# DDS_OUT_channel.net
KiCad netlist of a schematic drawn in Altium Designer
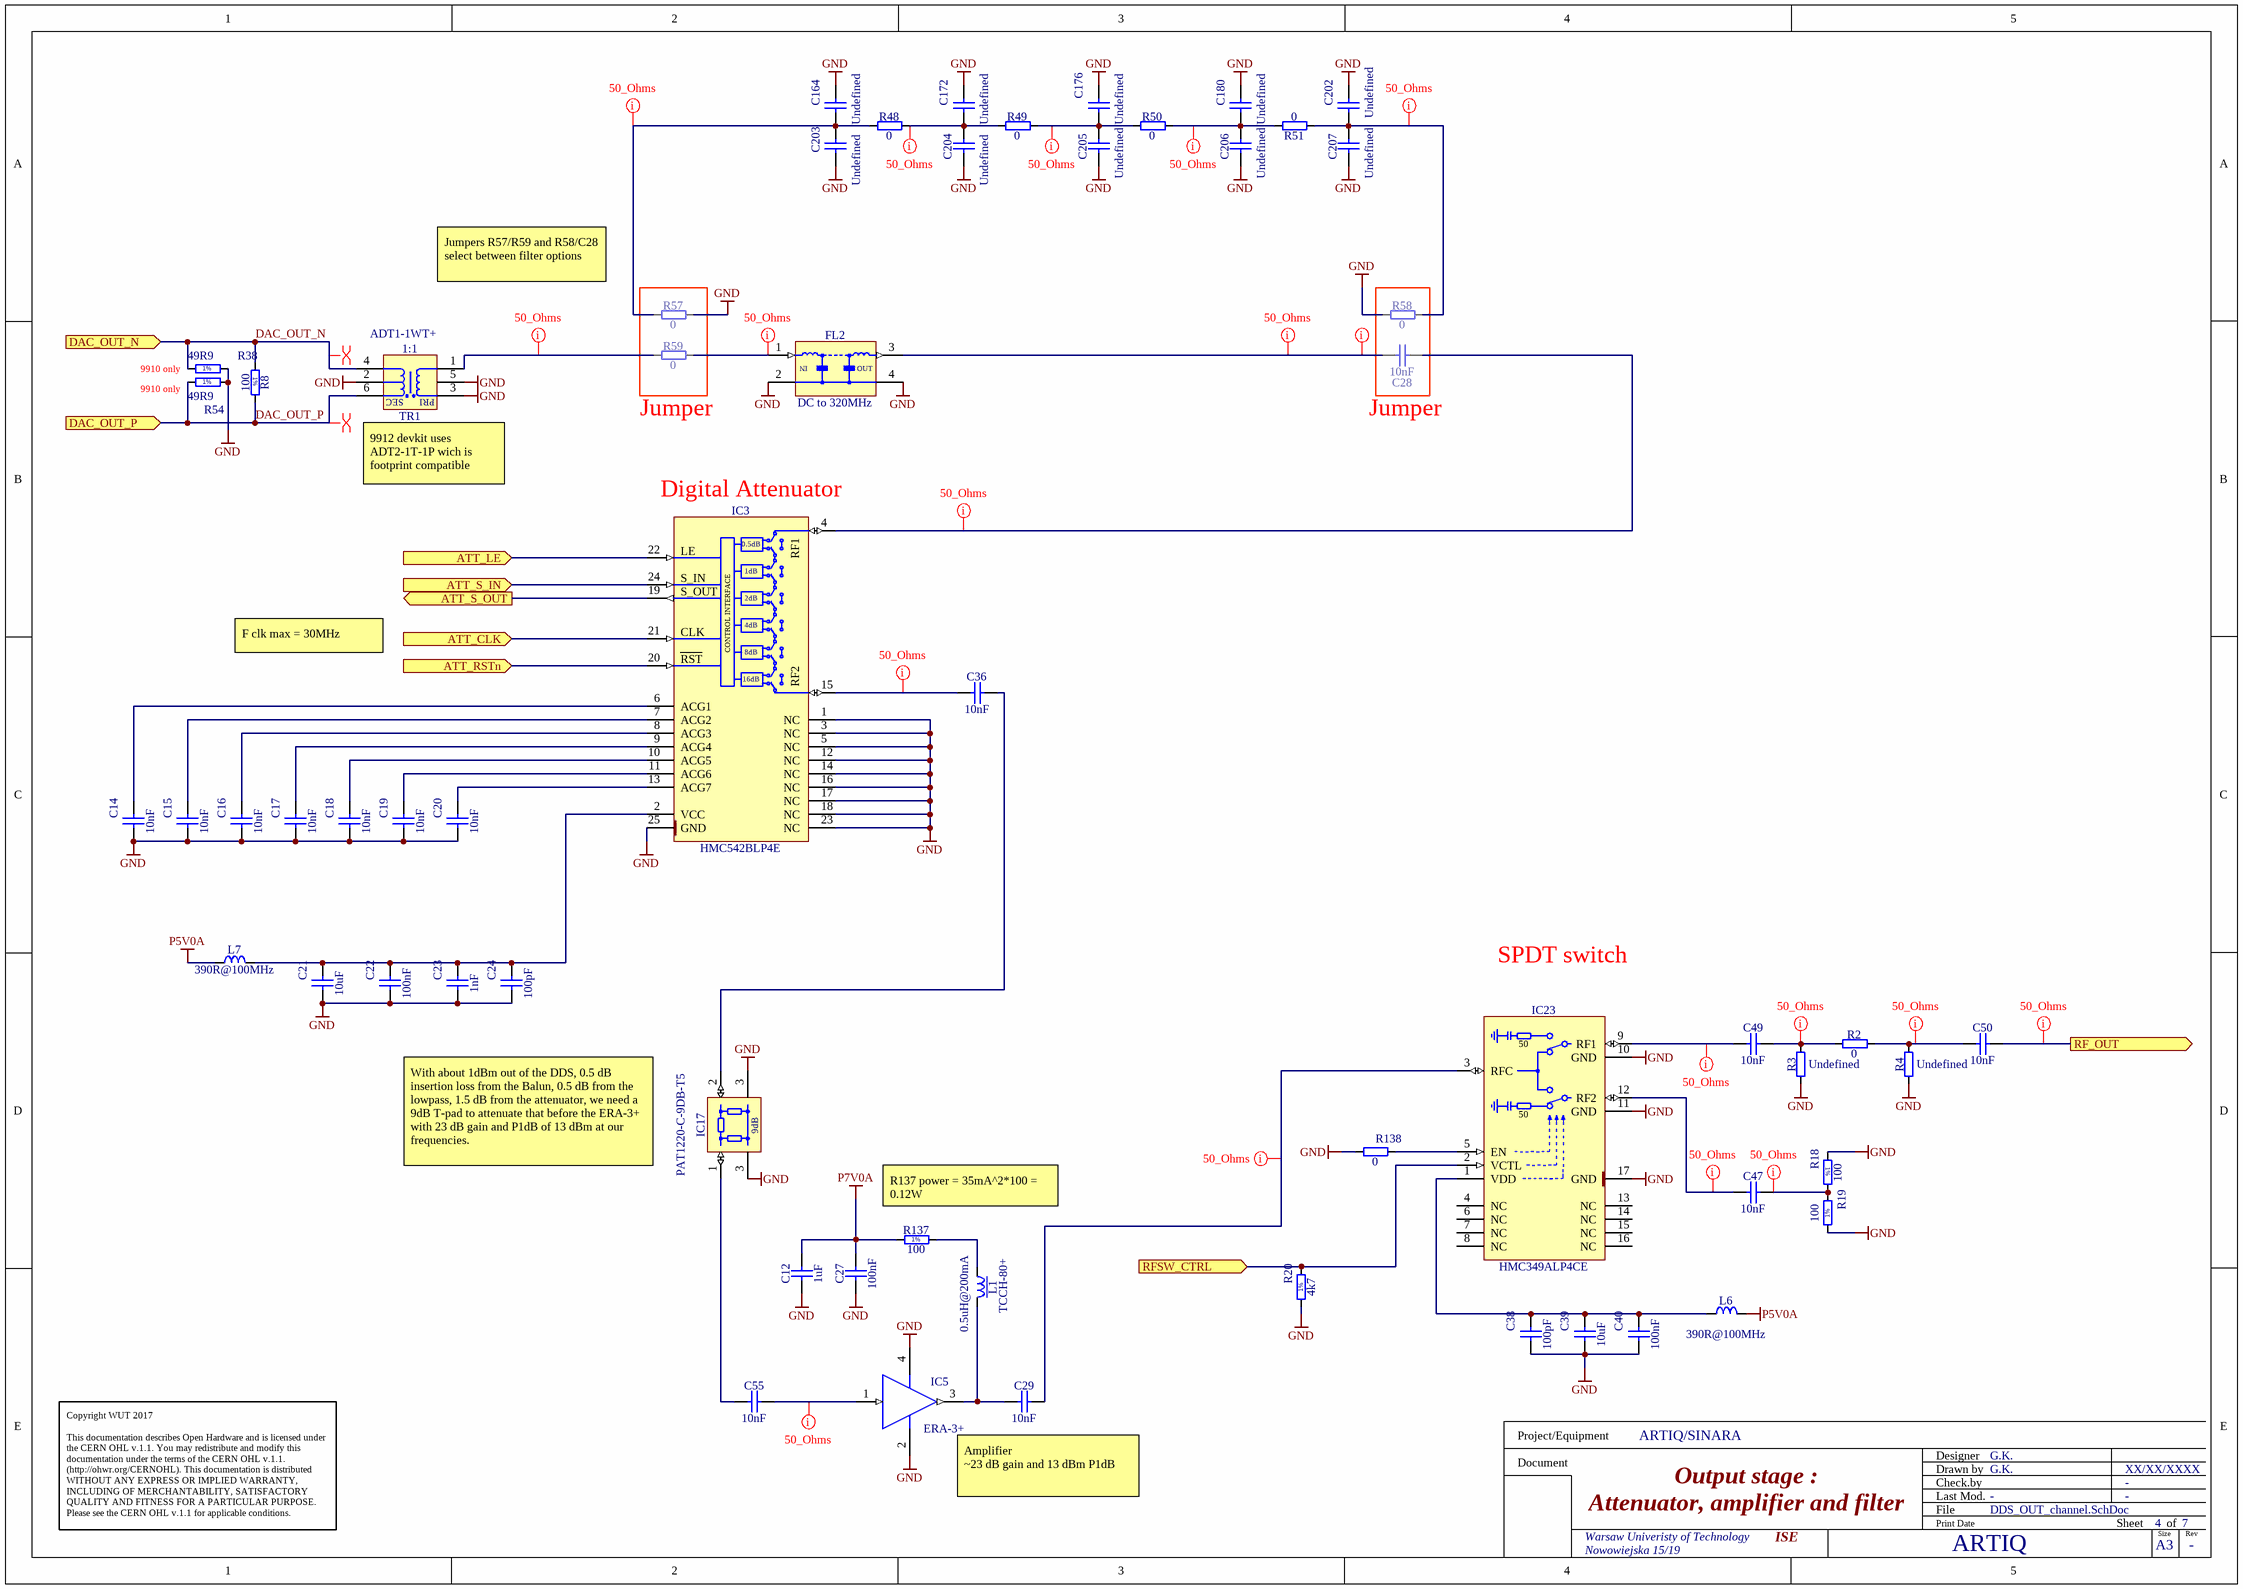
[diagram p0: DDS_OUT_channel.SchDoc]

(export (version "E")
  (design (tool "Eeschema 10.0.6"))
  (components
    (comp (ref "C12")
      (value "1uF")
      (footprint "CAPC2012X140N")
      (description "Non-polarised capacitor")
      (fields
        (field (name "PART NUMBER") "CC0805_1UF_35V_20%_X7R")
        (field (name "VOLTAGE") "35V")
        (field (name "AUTHOR") "CERN DEM JLC")
      )
      (libsource (lib "Capacitors") (part "Capacitor - non polarized"))
    )
    (comp (ref "C14")
      (value "10nF")
      (footprint "CAPC1005X55N")
      (description "Non-polarised capacitor")
      (fields
        (field (name "PART NUMBER") "CC0402_10NF_16V_10%_X7R")
        (field (name "VOLTAGE") "16V")
        (field (name "AUTHOR") "CERN DEM JLC")
      )
      (libsource (lib "Capacitors") (part "Capacitor - non polarized"))
    )
    (comp (ref "C15")
      (value "10nF")
      (footprint "CAPC1005X55N")
      (description "Non-polarised capacitor")
      (fields
        (field (name "PART NUMBER") "CC0402_10NF_16V_10%_X7R")
        (field (name "VOLTAGE") "16V")
        (field (name "AUTHOR") "CERN DEM JLC")
      )
      (libsource (lib "Capacitors") (part "Capacitor - non polarized"))
    )
    (comp (ref "C16")
      (value "10nF")
      (footprint "CAPC1005X55N")
      (description "Non-polarised capacitor")
      (fields
        (field (name "PART NUMBER") "CC0402_10NF_16V_10%_X7R")
        (field (name "VOLTAGE") "16V")
        (field (name "AUTHOR") "CERN DEM JLC")
      )
      (libsource (lib "Capacitors") (part "Capacitor - non polarized"))
    )
    (comp (ref "C17")
      (value "10nF")
      (footprint "CAPC1005X55N")
      (description "Non-polarised capacitor")
      (fields
        (field (name "PART NUMBER") "CC0402_10NF_16V_10%_X7R")
        (field (name "VOLTAGE") "16V")
        (field (name "AUTHOR") "CERN DEM JLC")
      )
      (libsource (lib "Capacitors") (part "Capacitor - non polarized"))
    )
    (comp (ref "C18")
      (value "10nF")
      (footprint "CAPC1005X55N")
      (description "Non-polarised capacitor")
      (fields
        (field (name "PART NUMBER") "CC0402_10NF_16V_10%_X7R")
        (field (name "VOLTAGE") "16V")
        (field (name "AUTHOR") "CERN DEM JLC")
      )
      (libsource (lib "Capacitors") (part "Capacitor - non polarized"))
    )
    (comp (ref "C19")
      (value "10nF")
      (footprint "CAPC1005X55N")
      (description "Non-polarised capacitor")
      (fields
        (field (name "PART NUMBER") "CC0402_10NF_16V_10%_X7R")
        (field (name "VOLTAGE") "16V")
        (field (name "AUTHOR") "CERN DEM JLC")
      )
      (libsource (lib "Capacitors") (part "Capacitor - non polarized"))
    )
    (comp (ref "C20")
      (value "10nF")
      (footprint "CAPC1005X55N")
      (description "Non-polarised capacitor")
      (fields
        (field (name "PART NUMBER") "CC0402_10NF_16V_10%_X7R")
        (field (name "VOLTAGE") "16V")
        (field (name "AUTHOR") "CERN DEM JLC")
      )
      (libsource (lib "Capacitors") (part "Capacitor - non polarized"))
    )
    (comp (ref "C21")
      (value "10uF")
      (footprint "CAPC1608X80N")
      (description "Non-polarised capacitor")
      (fields
        (field (name "PART NUMBER") "CC0603_10UF_16V_20%_X5R")
        (field (name "VOLTAGE") "16V")
        (field (name "AUTHOR") "CERN DEM MR")
      )
      (libsource (lib "Capacitors") (part "Capacitor - non polarized"))
    )
    (comp (ref "C22")
      (value "100nF")
      (footprint "CAPC1005X55N")
      (description "Non-polarised capacitor")
      (fields
        (field (name "PART NUMBER") "CC0402_100NF_16V_10%_X7R")
        (field (name "VOLTAGE") "16V")
        (field (name "AUTHOR") "CERN DEM JLC")
      )
      (libsource (lib "Capacitors") (part "Capacitor - non polarized"))
    )
    (comp (ref "C23")
      (value "1nF")
      (footprint "CAPC1005X55N")
      (description "Non-polarised capacitor")
      (fields
        (field (name "PART NUMBER") "CC0402_1NF_50V_10%_X7R")
        (field (name "VOLTAGE") "50V")
        (field (name "AUTHOR") "CERN DEM JLC")
      )
      (libsource (lib "Capacitors") (part "Capacitor - non polarized"))
    )
    (comp (ref "C24")
      (value "100pF")
      (footprint "CAPC1005X55N")
      (description "Non-polarised capacitor")
      (fields
        (field (name "PART NUMBER") "CC0402_100PF_50V_5%_C0G")
        (field (name "VOLTAGE") "50V")
        (field (name "AUTHOR") "CERN DEM JLC")
      )
      (libsource (lib "Capacitors") (part "Capacitor - non polarized"))
    )
    (comp (ref "C27")
      (value "100nF")
      (footprint "CAPC1005X55N")
      (description "Non-polarised capacitor")
      (fields
        (field (name "PART NUMBER") "CC0402_100NF_16V_10%_X5R")
        (field (name "VOLTAGE") "16V")
        (field (name "AUTHOR") "CERN DEM JLC")
      )
      (libsource (lib "Capacitors") (part "Capacitor - non polarized"))
    )
    (comp (ref "C28")
      (value "10nF")
      (footprint "CAPC1005X55N")
      (description "Non-polarised capacitor")
      (fields
        (field (name "PART NUMBER") "CC0402_10NF_16V_10%_X7R")
        (field (name "VOLTAGE") "16V")
        (field (name "AUTHOR") "CERN DEM JLC")
      )
      (libsource (lib "Capacitors") (part "Capacitor - non polarized"))
    )
    (comp (ref "C29")
      (value "10nF")
      (footprint "CAPC1005X55N")
      (description "Non-polarised capacitor")
      (fields
        (field (name "PART NUMBER") "CC0402_10NF_16V_10%_X7R")
        (field (name "VOLTAGE") "16V")
        (field (name "AUTHOR") "CERN DEM JLC")
      )
      (libsource (lib "Capacitors") (part "Capacitor - non polarized"))
    )
    (comp (ref "C36")
      (value "10nF")
      (footprint "CAPC1005X55N")
      (description "Non-polarised capacitor")
      (fields
        (field (name "PART NUMBER") "CC0402_10NF_16V_10%_X7R")
        (field (name "VOLTAGE") "16V")
        (field (name "AUTHOR") "CERN DEM JLC")
      )
      (libsource (lib "Capacitors") (part "Capacitor - non polarized"))
    )
    (comp (ref "C38")
      (value "100pF")
      (footprint "CAPC1005X55N")
      (description "Non-polarised capacitor")
      (fields
        (field (name "PART NUMBER") "CC0402_100PF_50V_5%_C0G")
        (field (name "VOLTAGE") "50V")
        (field (name "AUTHOR") "CERN DEM JLC")
      )
      (libsource (lib "Capacitors") (part "Capacitor - non polarized"))
    )
    (comp (ref "C39")
      (value "10uF")
      (footprint "CAPC1608X80N")
      (description "Non-polarised capacitor")
      (fields
        (field (name "PART NUMBER") "CC0603_10UF_16V_20%_X5R")
        (field (name "VOLTAGE") "16V")
        (field (name "AUTHOR") "CERN DEM MR")
      )
      (libsource (lib "Capacitors") (part "Capacitor - non polarized"))
    )
    (comp (ref "C40")
      (value "100nF")
      (footprint "CAPC1005X55N")
      (description "Non-polarised capacitor")
      (fields
        (field (name "PART NUMBER") "CC0402_100NF_16V_10%_X5R")
        (field (name "VOLTAGE") "16V")
        (field (name "AUTHOR") "CERN DEM JLC")
      )
      (libsource (lib "Capacitors") (part "Capacitor - non polarized"))
    )
    (comp (ref "C47")
      (value "10nF")
      (footprint "CAPC1005X55N")
      (description "Non-polarised capacitor")
      (fields
        (field (name "PART NUMBER") "CC0402_10NF_16V_10%_X7R")
        (field (name "VOLTAGE") "16V")
        (field (name "AUTHOR") "CERN DEM JLC")
      )
      (libsource (lib "Capacitors") (part "Capacitor - non polarized"))
    )
    (comp (ref "C49")
      (value "10nF")
      (footprint "CAPC1005X55N")
      (description "Non-polarised capacitor")
      (fields
        (field (name "PART NUMBER") "CC0402_10NF_16V_10%_X7R")
        (field (name "VOLTAGE") "16V")
        (field (name "AUTHOR") "CERN DEM JLC")
      )
      (libsource (lib "Capacitors") (part "Capacitor - non polarized"))
    )
    (comp (ref "C50")
      (value "10nF")
      (footprint "CAPC1005X55N")
      (description "Non-polarised capacitor")
      (fields
        (field (name "PART NUMBER") "CC0402_10NF_16V_10%_X7R")
        (field (name "VOLTAGE") "16V")
        (field (name "AUTHOR") "CERN DEM JLC")
      )
      (libsource (lib "Capacitors") (part "Capacitor - non polarized"))
    )
    (comp (ref "C55")
      (value "10nF")
      (footprint "CAPC1005X55N")
      (description "Non-polarised capacitor")
      (fields
        (field (name "PART NUMBER") "CC0402_10NF_16V_10%_X7R")
        (field (name "VOLTAGE") "16V")
        (field (name "AUTHOR") "CERN DEM JLC")
      )
      (libsource (lib "Capacitors") (part "Capacitor - non polarized"))
    )
    (comp (ref "C164")
      (value "Undefined")
      (footprint "CAPC1005X55N")
      (description "Non-polarised capacitor")
      (fields (field (name "PART NUMBER") "CC0402_NO-VALUE") (field (name "AUTHOR") "CERN DEM JLC"))
      (libsource (lib "Capacitors") (part "Capacitor - non polarized"))
    )
    (comp (ref "C172")
      (value "Undefined")
      (footprint "CAPC1005X55N")
      (description "Non-polarised capacitor")
      (fields (field (name "PART NUMBER") "CC0402_NO-VALUE") (field (name "AUTHOR") "CERN DEM JLC"))
      (libsource (lib "Capacitors") (part "Capacitor - non polarized"))
    )
    (comp (ref "C176")
      (value "Undefined")
      (footprint "CAPC1005X55N")
      (description "Non-polarised capacitor")
      (fields (field (name "PART NUMBER") "CC0402_NO-VALUE") (field (name "AUTHOR") "CERN DEM JLC"))
      (libsource (lib "Capacitors") (part "Capacitor - non polarized"))
    )
    (comp (ref "C180")
      (value "Undefined")
      (footprint "CAPC1005X55N")
      (description "Non-polarised capacitor")
      (fields (field (name "PART NUMBER") "CC0402_NO-VALUE") (field (name "AUTHOR") "CERN DEM JLC"))
      (libsource (lib "Capacitors") (part "Capacitor - non polarized"))
    )
    (comp (ref "C202")
      (value "Undefined")
      (footprint "CAPC1005X55N")
      (description "Non-polarised capacitor")
      (fields (field (name "PART NUMBER") "CC0402_NO-VALUE") (field (name "AUTHOR") "CERN DEM JLC"))
      (libsource (lib "Capacitors") (part "Capacitor - non polarized"))
    )
    (comp (ref "C203")
      (value "Undefined")
      (footprint "CAPC1005X55N")
      (description "Non-polarised capacitor")
      (fields (field (name "PART NUMBER") "CC0402_NO-VALUE") (field (name "AUTHOR") "CERN DEM JLC"))
      (libsource (lib "Capacitors") (part "Capacitor - non polarized"))
    )
    (comp (ref "C204")
      (value "Undefined")
      (footprint "CAPC1005X55N")
      (description "Non-polarised capacitor")
      (fields (field (name "PART NUMBER") "CC0402_NO-VALUE") (field (name "AUTHOR") "CERN DEM JLC"))
      (libsource (lib "Capacitors") (part "Capacitor - non polarized"))
    )
    (comp (ref "C205")
      (value "Undefined")
      (footprint "CAPC1005X55N")
      (description "Non-polarised capacitor")
      (fields (field (name "PART NUMBER") "CC0402_NO-VALUE") (field (name "AUTHOR") "CERN DEM JLC"))
      (libsource (lib "Capacitors") (part "Capacitor - non polarized"))
    )
    (comp (ref "C206")
      (value "Undefined")
      (footprint "CAPC1005X55N")
      (description "Non-polarised capacitor")
      (fields (field (name "PART NUMBER") "CC0402_NO-VALUE") (field (name "AUTHOR") "CERN DEM JLC"))
      (libsource (lib "Capacitors") (part "Capacitor - non polarized"))
    )
    (comp (ref "C207")
      (value "Undefined")
      (footprint "CAPC1005X55N")
      (description "Non-polarised capacitor")
      (fields (field (name "PART NUMBER") "CC0402_NO-VALUE") (field (name "AUTHOR") "CERN DEM JLC"))
      (libsource (lib "Capacitors") (part "Capacitor - non polarized"))
    )
    (comp (ref "FL2")
      (value "DC to 320MHz")
      (footprint "FIL_MINI-CIRCUITS_FV1206")
      (description "50 Ohm DC to 320MHz Low Pass Filter")
      (fields
        (field (name "PART NUMBER") "FIL_MINI-CIRCUITS_LFCN-320")
        (field (name "MANUFACTURER") "MINI-CIRCUITS")
        (field (name "AUTHOR") "CERN DEM JLC")
      )
      (libsource (lib "LIBRARY_SCH") (part "FIL_MINI-CIRCUITS_LFCN-320"))
    )
    (comp (ref "IC3")
      (value "HMC542BLP4E")
      (footprint "QFN50P400X400X100-25N-S295")
      (description "0.5dB LSB GaAs MMIC 6-bit Digital Serial Control Attenuator, DC - 4GHz")
      (fields (field (name "MANUFACTURER") "HITTITE MICROWAVE CORP") (field (name "AUTHOR") "CERN DEM JMW"))
      (libsource (lib "ICs And Semiconductors") (part "HMC542BLP4E"))
    )
    (comp (ref "IC5")
      (value "ERA-3+")
      (footprint "MINI-CIRCUITS_WW107")
      (description "DC-3GHz Monolithic Amplifier")
      (fields (field (name "MANUFACTURER") "MINI-CIRCUITS") (field (name "AUTHOR") "GK"))
      (libsource (lib "LIBRARY_SCH") (part "RF_ERA-3+"))
    )
    (comp (ref "IC17")
      (value "PAT1220-C-9DB-T5")
      (footprint "SUSUMU_PAT1220")
      (description "DC to 10GHz, 100mw, 50 Ohm, 9dB, Precision chip attenuator")
      (fields (field (name "MANUFACTURER") "SUSUMU") (field (name "AUTHOR") "GK"))
      (libsource (lib "LIBRARY_SCH") (part "RF_PAT1220-C-9DB-T5"))
    )
    (comp (ref "IC23")
      (value "HMC349ALP4CE")
      (footprint "QFN65P400X400X100-17N-S255")
      (description "DC-4GHz High Isolation SPDT Non-Reflective Switch")
      (fields (field (name "MANUFACTURER") "ANALOG DEVICES") (field (name "AUTHOR") "CERN DEM JLC"))
      (libsource (lib "ICs And Semiconductors") (part "HMC349ALP4CE"))
    )
    (comp (ref "L1")
      (value "0.5uH@200mA")
      (footprint "IND_MINI-CIRCUITS_GU1604")
      (description "50 Ohms, 50 to 8200 MHz RF Choke")
      (fields
        (field (name "PART NUMBER") "IND_MINI-CIRCUITS_TCCH-80+")
        (field (name "POWER") "200mA")
        (field (name "MANUFACTURER PART NUMBER") "TCCH-80+")
        (field (name "AUTHOR") "CERN DEM JLC")
      )
      (libsource (lib "Inductors & Transformers") (part "IND_MINI-CIRCUITS_TCCH-80+"))
    )
    (comp (ref "L6")
      (value "390R@100MHz")
      (footprint "INDC1608X95N")
      (description "Inductor")
      (fields
        (field (name "PART NUMBER") "IND0603_TDK_MPZ1608R391A")
        (field (name "POWER") "1.2A")
        (field (name "AUTHOR") "CERN DEM JLC")
      )
      (libsource (lib "Inductors & Transformers") (part "Inductor"))
    )
    (comp (ref "L7")
      (value "390R@100MHz")
      (footprint "INDC1608X95N")
      (description "Inductor")
      (fields
        (field (name "PART NUMBER") "IND0603_TDK_MPZ1608R391A")
        (field (name "POWER") "1.2A")
        (field (name "AUTHOR") "CERN DEM JLC")
      )
      (libsource (lib "Inductors & Transformers") (part "Inductor"))
    )
    (comp (ref "R2")
      (value "0")
      (footprint "RESC1005X40N")
      (description "Resistor")
      (fields
        (field (name "PART NUMBER") "R0402_0R_JUMPER")
        (field (name "MANUFACTURER") "GENERIC")
        (field (name "AUTHOR") "CERN DEM JLC")
      )
      (libsource (lib "Resistors") (part "Resistor"))
    )
    (comp (ref "R3")
      (value "Undefined")
      (footprint "RESC1005X40N")
      (description "Resistor")
      (fields (field (name "PART NUMBER") "R0402_NO-VALUE") (field (name "AUTHOR") "CERN DEM JLC"))
      (libsource (lib "Resistors") (part "Resistor"))
    )
    (comp (ref "R4")
      (value "Undefined")
      (footprint "RESC1005X40N")
      (description "Resistor")
      (fields (field (name "PART NUMBER") "R0402_NO-VALUE") (field (name "AUTHOR") "CERN DEM JLC"))
      (libsource (lib "Resistors") (part "Resistor"))
    )
    (comp (ref "R8")
      (value "100")
      (footprint "RESC1005X40N")
      (description "Resistor - 1%")
      (fields
        (field (name "PART NUMBER") "R0402_100R_1%_0.0625W_100PPM")
        (field (name "POWER") "0.0625W")
        (field (name "AUTHOR") "CERN DEM JLC")
      )
      (libsource (lib "Resistors") (part "Resistor - 1%"))
    )
    (comp (ref "R18")
      (value "100")
      (footprint "RESC1005X40N")
      (description "Resistor - 1%")
      (fields
        (field (name "PART NUMBER") "R0402_100R_1%_0.0625W_100PPM")
        (field (name "POWER") "0.0625W")
        (field (name "AUTHOR") "CERN DEM JLC")
      )
      (libsource (lib "Resistors") (part "Resistor - 1%"))
    )
    (comp (ref "R19")
      (value "100")
      (footprint "RESC1005X40N")
      (description "Resistor - 1%")
      (fields
        (field (name "PART NUMBER") "R0402_100R_1%_0.0625W_100PPM")
        (field (name "POWER") "0.0625W")
        (field (name "AUTHOR") "CERN DEM JLC")
      )
      (libsource (lib "Resistors") (part "Resistor - 1%"))
    )
    (comp (ref "R20")
      (value "4k7")
      (footprint "RESC1005X40N")
      (description "Resistor - 1%")
      (fields
        (field (name "PART NUMBER") "R0402_4K7_1%_0.0625W_100PPM")
        (field (name "POWER") "0.0625W")
        (field (name "AUTHOR") "CERN DEM JLC")
      )
      (libsource (lib "Resistors") (part "Resistor - 1%"))
    )
    (comp (ref "R38")
      (value "49R9")
      (footprint "RESC1005X40N")
      (description "Resistor - 1%")
      (fields
        (field (name "PART NUMBER") "R0402_49R9_1%_0.0625W_100PPM")
        (field (name "POWER") "0.0625W")
        (field (name "AUTHOR") "CERN DEM JLC")
      )
      (libsource (lib "Resistors") (part "Resistor - 1%"))
    )
    (comp (ref "R48")
      (value "0")
      (footprint "RESC1005X40N")
      (description "Resistor")
      (fields
        (field (name "PART NUMBER") "R0402_0R_JUMPER")
        (field (name "MANUFACTURER") "GENERIC")
        (field (name "AUTHOR") "CERN DEM JLC")
      )
      (libsource (lib "Resistors") (part "Resistor"))
    )
    (comp (ref "R49")
      (value "0")
      (footprint "RESC1005X40N")
      (description "Resistor")
      (fields
        (field (name "PART NUMBER") "R0402_0R_JUMPER")
        (field (name "MANUFACTURER") "GENERIC")
        (field (name "AUTHOR") "CERN DEM JLC")
      )
      (libsource (lib "Resistors") (part "Resistor"))
    )
    (comp (ref "R50")
      (value "0")
      (footprint "RESC1005X40N")
      (description "Resistor")
      (fields
        (field (name "PART NUMBER") "R0402_0R_JUMPER")
        (field (name "MANUFACTURER") "GENERIC")
        (field (name "AUTHOR") "CERN DEM JLC")
      )
      (libsource (lib "Resistors") (part "Resistor"))
    )
    (comp (ref "R51")
      (value "0")
      (footprint "RESC1005X40N")
      (description "Resistor")
      (fields
        (field (name "PART NUMBER") "R0402_0R_JUMPER")
        (field (name "MANUFACTURER") "GENERIC")
        (field (name "AUTHOR") "CERN DEM JLC")
      )
      (libsource (lib "Resistors") (part "Resistor"))
    )
    (comp (ref "R54")
      (value "49R9")
      (footprint "RESC1005X40N")
      (description "Resistor - 1%")
      (fields
        (field (name "PART NUMBER") "R0402_49R9_1%_0.0625W_100PPM")
        (field (name "POWER") "0.0625W")
        (field (name "AUTHOR") "CERN DEM JLC")
      )
      (libsource (lib "Resistors") (part "Resistor - 1%"))
    )
    (comp (ref "R57")
      (value "0")
      (footprint "RESC1005X40N")
      (description "Resistor")
      (fields
        (field (name "PART NUMBER") "R0402_0R_JUMPER")
        (field (name "MANUFACTURER") "GENERIC")
        (field (name "AUTHOR") "CERN DEM JLC")
      )
      (libsource (lib "Resistors") (part "Resistor"))
    )
    (comp (ref "R58")
      (value "0")
      (footprint "RESC1005X40N")
      (description "Resistor")
      (fields
        (field (name "PART NUMBER") "R0402_0R_JUMPER")
        (field (name "MANUFACTURER") "GENERIC")
        (field (name "AUTHOR") "CERN DEM JLC")
      )
      (libsource (lib "Resistors") (part "Resistor"))
    )
    (comp (ref "R59")
      (value "0")
      (footprint "RESC1005X40N")
      (description "Resistor")
      (fields
        (field (name "PART NUMBER") "R0402_0R_JUMPER")
        (field (name "MANUFACTURER") "GENERIC")
        (field (name "AUTHOR") "CERN DEM JLC")
      )
      (libsource (lib "Resistors") (part "Resistor"))
    )
    (comp (ref "R137")
      (value "100")
      (footprint "RESC3216X65N")
      (description "Resistor - 1%")
      (fields
        (field (name "PART NUMBER") "R1206_100R_1%_0.5W_100PPM_VISHAY_CRCW-HP e3")
        (field (name "POWER") "0.5W")
        (field (name "AUTHOR") "CERN DEM JLC")
      )
      (libsource (lib "Resistors") (part "Resistor - 1%"))
    )
    (comp (ref "R138")
      (value "0")
      (footprint "RESC1005X40N")
      (description "Resistor")
      (fields
        (field (name "PART NUMBER") "R0402_0R_JUMPER")
        (field (name "MANUFACTURER") "GENERIC")
        (field (name "AUTHOR") "CERN DEM JLC")
      )
      (libsource (lib "Resistors") (part "Resistor"))
    )
    (comp (ref "TR1")
      (value "1:1")
      (footprint "XFMR_MINI-CIRCUITS_CD542")
      (description "75 Ohm 0.4 To 800MHz RF Transformers")
      (fields
        (field (name "PART NUMBER") "XFMR_MINI-CIRCUITS_ADT1-1WT+")
        (field (name "MANUFACTURER") "MINI-CIRCUITS")
        (field (name "MANUFACTURER PART NUMBER") "ADT1-1WT+")
        (field (name "AUTHOR") "CERN DEM JLC")
      )
      (libsource (lib "Inductors & Transformers") (part "XFMR_MINI-CIRCUITS_ADT1-1WT+"))
    )
  )
  (nets
    (net (code "1") (name "/ATT_CLK") (class "Default")
      (node (ref "IC3") (pin "21") (pinfunction "SHIFT_CLOCK_21") (pintype "input"))
    )
    (net (code "2") (name "/ATT_LE") (class "Default")
      (node (ref "IC3") (pin "22") (pinfunction "LATCH_ENABLE_22") (pintype "input"))
    )
    (net (code "3") (name "/ATT_RSTn") (class "Default")
      (node (ref "IC3") (pin "20") (pinfunction "~{RESET}_20") (pintype "input"))
    )
    (net (code "4") (name "/ATT_S_IN") (class "Default")
      (node (ref "IC3") (pin "24") (pinfunction "SERIAL_INPUT_24") (pintype "input"))
    )
    (net (code "5") (name "/ATT_S_OUT") (class "Default")
      (node (ref "IC3") (pin "19") (pinfunction "SERIAL_OUTPUT_19") (pintype "output"))
    )
    (net (code "6") (name "/DAC_OUT_N") (class "Default")
      (node (ref "R38") (pin "1") (pinfunction "1_1") (pintype "passive"))
      (node (ref "R8") (pin "1") (pinfunction "1_1") (pintype "passive"))
      (node (ref "TR1") (pin "4") (pinfunction "S_4") (pintype "passive"))
    )
    (net (code "7") (name "/DAC_OUT_P") (class "Default")
      (node (ref "R54") (pin "1") (pinfunction "1_1") (pintype "passive"))
      (node (ref "R8") (pin "2") (pinfunction "2_2") (pintype "passive"))
      (node (ref "TR1") (pin "6") (pinfunction "SDOT_6") (pintype "passive"))
    )
    (net (code "8") (name "/RFSW_CTRL") (class "Default")
      (node (ref "IC23") (pin "2") (pinfunction "VCTL_2") (pintype "input"))
      (node (ref "R20") (pin "2") (pinfunction "2_2") (pintype "passive"))
    )
    (net (code "9") (name "/RF_OUT") (class "Default")
      (node (ref "C50") (pin "2") (pinfunction "2_2") (pintype "passive"))
    )
    (net (code "10") (name "GND") (class "Default")
      (node (ref "C12") (pin "1") (pinfunction "1_1") (pintype "passive"))
      (node (ref "C14") (pin "1") (pinfunction "1_1") (pintype "passive"))
      (node (ref "C15") (pin "1") (pinfunction "1_1") (pintype "passive"))
      (node (ref "C16") (pin "1") (pinfunction "1_1") (pintype "passive"))
      (node (ref "C164") (pin "2") (pinfunction "2_2") (pintype "passive"))
      (node (ref "C17") (pin "1") (pinfunction "1_1") (pintype "passive"))
      (node (ref "C172") (pin "2") (pinfunction "2_2") (pintype "passive"))
      (node (ref "C176") (pin "2") (pinfunction "2_2") (pintype "passive"))
      (node (ref "C18") (pin "1") (pinfunction "1_1") (pintype "passive"))
      (node (ref "C180") (pin "2") (pinfunction "2_2") (pintype "passive"))
      (node (ref "C19") (pin "1") (pinfunction "1_1") (pintype "passive"))
      (node (ref "C20") (pin "1") (pinfunction "1_1") (pintype "passive"))
      (node (ref "C202") (pin "2") (pinfunction "2_2") (pintype "passive"))
      (node (ref "C203") (pin "1") (pinfunction "1_1") (pintype "passive"))
      (node (ref "C204") (pin "1") (pinfunction "1_1") (pintype "passive"))
      (node (ref "C205") (pin "1") (pinfunction "1_1") (pintype "passive"))
      (node (ref "C206") (pin "1") (pinfunction "1_1") (pintype "passive"))
      (node (ref "C207") (pin "1") (pinfunction "1_1") (pintype "passive"))
      (node (ref "C21") (pin "1") (pinfunction "1_1") (pintype "passive"))
      (node (ref "C22") (pin "1") (pinfunction "1_1") (pintype "passive"))
      (node (ref "C23") (pin "1") (pinfunction "1_1") (pintype "passive"))
      (node (ref "C24") (pin "1") (pinfunction "1_1") (pintype "passive"))
      (node (ref "C27") (pin "1") (pinfunction "1_1") (pintype "passive"))
      (node (ref "C38") (pin "2") (pinfunction "2_2") (pintype "passive"))
      (node (ref "C39") (pin "1") (pinfunction "1_1") (pintype "passive"))
      (node (ref "C40") (pin "1") (pinfunction "1_1") (pintype "passive"))
      (node (ref "FL2") (pin "2") (pinfunction "GND_2") (pintype "power_in"))
      (node (ref "FL2") (pin "4") (pinfunction "GND_4") (pintype "power_in"))
      (node (ref "IC17") (pin "3") (pinfunction "GND_3") (pintype "passive"))
      (node (ref "IC23") (pin "10") (pinfunction "GND_10") (pintype "power_in"))
      (node (ref "IC23") (pin "11") (pinfunction "GND_11") (pintype "power_in"))
      (node (ref "IC23") (pin "17") (pinfunction "GND_17") (pintype "power_in"))
      (node (ref "IC3") (pin "1") (pinfunction "NC_1") (pintype "passive"))
      (node (ref "IC3") (pin "12") (pinfunction "NC_12") (pintype "passive"))
      (node (ref "IC3") (pin "14") (pinfunction "NC_14") (pintype "passive"))
      (node (ref "IC3") (pin "16") (pinfunction "NC_16") (pintype "passive"))
      (node (ref "IC3") (pin "17") (pinfunction "NC_17") (pintype "passive"))
      (node (ref "IC3") (pin "18") (pinfunction "NC_18") (pintype "passive"))
      (node (ref "IC3") (pin "23") (pinfunction "NC_23") (pintype "passive"))
      (node (ref "IC3") (pin "25") (pinfunction "GND_25") (pintype "power_in"))
      (node (ref "IC3") (pin "3") (pinfunction "NC_3") (pintype "passive"))
      (node (ref "IC3") (pin "5") (pinfunction "NC_5") (pintype "passive"))
      (node (ref "IC5") (pin "2") (pinfunction "GND_2") (pintype "power_in"))
      (node (ref "IC5") (pin "4") (pinfunction "GND_4") (pintype "power_in"))
      (node (ref "R138") (pin "1") (pinfunction "1_1") (pintype "passive"))
      (node (ref "R18") (pin "1") (pinfunction "1_1") (pintype "passive"))
      (node (ref "R19") (pin "1") (pinfunction "1_1") (pintype "passive"))
      (node (ref "R20") (pin "1") (pinfunction "1_1") (pintype "passive"))
      (node (ref "R3") (pin "1") (pinfunction "1_1") (pintype "passive"))
      (node (ref "R38") (pin "2") (pinfunction "2_2") (pintype "passive"))
      (node (ref "R4") (pin "1") (pinfunction "1_1") (pintype "passive"))
      (node (ref "R54") (pin "2") (pinfunction "2_2") (pintype "passive"))
      (node (ref "R57") (pin "2") (pinfunction "2_2") (pintype "passive"))
      (node (ref "R58") (pin "2") (pinfunction "2_2") (pintype "passive"))
      (node (ref "TR1") (pin "2") (pinfunction "SCT_2") (pintype "passive"))
      (node (ref "TR1") (pin "3") (pinfunction "PDOT_3") (pintype "passive"))
      (node (ref "TR1") (pin "5") (pinfunction "NC_5") (pintype "passive"))
    )
    (net (code "11") (name "Net-(C47-Pad2)") (class "Default")
      (node (ref "C47") (pin "2") (pinfunction "2_2") (pintype "passive"))
      (node (ref "R18") (pin "2") (pinfunction "2_2") (pintype "passive"))
      (node (ref "R19") (pin "2") (pinfunction "2_2") (pintype "passive"))
    )
    (net (code "12") (name "Net-(C49-Pad2)") (class "Default")
      (node (ref "C49") (pin "2") (pinfunction "2_2") (pintype "passive"))
      (node (ref "R2") (pin "1") (pinfunction "1_1") (pintype "passive"))
      (node (ref "R3") (pin "2") (pinfunction "2_2") (pintype "passive"))
    )
    (net (code "13") (name "Net-(C50-Pad1)") (class "Default")
      (node (ref "C50") (pin "1") (pinfunction "1_1") (pintype "passive"))
      (node (ref "R2") (pin "2") (pinfunction "2_2") (pintype "passive"))
      (node (ref "R4") (pin "2") (pinfunction "2_2") (pintype "passive"))
    )
    (net (code "14") (name "Net-(C164-Pad1)") (class "Default")
      (node (ref "C164") (pin "1") (pinfunction "1_1") (pintype "passive"))
      (node (ref "C203") (pin "2") (pinfunction "2_2") (pintype "passive"))
      (node (ref "R48") (pin "1") (pinfunction "1_1") (pintype "passive"))
      (node (ref "R57") (pin "1") (pinfunction "1_1") (pintype "passive"))
    )
    (net (code "15") (name "Net-(C172-Pad1)") (class "Default")
      (node (ref "C172") (pin "1") (pinfunction "1_1") (pintype "passive"))
      (node (ref "C204") (pin "2") (pinfunction "2_2") (pintype "passive"))
      (node (ref "R48") (pin "2") (pinfunction "2_2") (pintype "passive"))
      (node (ref "R49") (pin "1") (pinfunction "1_1") (pintype "passive"))
    )
    (net (code "16") (name "Net-(C176-Pad1)") (class "Default")
      (node (ref "C176") (pin "1") (pinfunction "1_1") (pintype "passive"))
      (node (ref "C205") (pin "2") (pinfunction "2_2") (pintype "passive"))
      (node (ref "R49") (pin "2") (pinfunction "2_2") (pintype "passive"))
      (node (ref "R50") (pin "1") (pinfunction "1_1") (pintype "passive"))
    )
    (net (code "17") (name "Net-(C180-Pad1)") (class "Default")
      (node (ref "C180") (pin "1") (pinfunction "1_1") (pintype "passive"))
      (node (ref "C206") (pin "2") (pinfunction "2_2") (pintype "passive"))
      (node (ref "R50") (pin "2") (pinfunction "2_2") (pintype "passive"))
      (node (ref "R51") (pin "2") (pinfunction "2_2") (pintype "passive"))
    )
    (net (code "18") (name "Net-(C202-Pad1)") (class "Default")
      (node (ref "C202") (pin "1") (pinfunction "1_1") (pintype "passive"))
      (node (ref "C207") (pin "2") (pinfunction "2_2") (pintype "passive"))
      (node (ref "R51") (pin "1") (pinfunction "1_1") (pintype "passive"))
      (node (ref "R58") (pin "1") (pinfunction "1_1") (pintype "passive"))
    )
    (net (code "19") (name "Net-(FL2-RFIN)") (class "Default")
      (node (ref "FL2") (pin "1") (pinfunction "RFIN_1") (pintype "input"))
      (node (ref "R59") (pin "2") (pinfunction "2_2") (pintype "passive"))
    )
    (net (code "20") (name "Net-(FL2-RFOUT)") (class "Default")
      (node (ref "C28") (pin "1") (pinfunction "1_1") (pintype "passive"))
      (node (ref "FL2") (pin "3") (pinfunction "RFOUT_3") (pintype "output"))
    )
    (net (code "21") (name "Net-(IC3-ACG1)") (class "Default")
      (node (ref "C14") (pin "2") (pinfunction "2_2") (pintype "passive"))
      (node (ref "IC3") (pin "6") (pinfunction "ACG1_6") (pintype "passive"))
    )
    (net (code "22") (name "Net-(IC3-ACG2)") (class "Default")
      (node (ref "C15") (pin "2") (pinfunction "2_2") (pintype "passive"))
      (node (ref "IC3") (pin "7") (pinfunction "ACG2_7") (pintype "passive"))
    )
    (net (code "23") (name "Net-(IC3-ACG3)") (class "Default")
      (node (ref "C16") (pin "2") (pinfunction "2_2") (pintype "passive"))
      (node (ref "IC3") (pin "8") (pinfunction "ACG3_8") (pintype "passive"))
    )
    (net (code "24") (name "Net-(IC3-ACG4)") (class "Default")
      (node (ref "C17") (pin "2") (pinfunction "2_2") (pintype "passive"))
      (node (ref "IC3") (pin "9") (pinfunction "ACG4_9") (pintype "passive"))
    )
    (net (code "25") (name "Net-(IC3-ACG5)") (class "Default")
      (node (ref "C18") (pin "2") (pinfunction "2_2") (pintype "passive"))
      (node (ref "IC3") (pin "10") (pinfunction "ACG5_10") (pintype "passive"))
    )
    (net (code "26") (name "Net-(IC3-ACG6)") (class "Default")
      (node (ref "C19") (pin "2") (pinfunction "2_2") (pintype "passive"))
      (node (ref "IC3") (pin "11") (pinfunction "ACG6_11") (pintype "passive"))
    )
    (net (code "27") (name "Net-(IC3-ACG7)") (class "Default")
      (node (ref "C20") (pin "2") (pinfunction "2_2") (pintype "passive"))
      (node (ref "IC3") (pin "13") (pinfunction "ACG7_13") (pintype "passive"))
    )
    (net (code "28") (name "Net-(IC3-RF1)") (class "Default")
      (node (ref "C28") (pin "2") (pinfunction "2_2") (pintype "passive"))
      (node (ref "IC3") (pin "4") (pinfunction "RF1_4") (pintype "bidirectional"))
    )
    (net (code "29") (name "Net-(IC3-RF2)") (class "Default")
      (node (ref "C36") (pin "1") (pinfunction "1_1") (pintype "passive"))
      (node (ref "IC3") (pin "15") (pinfunction "RF2_15") (pintype "bidirectional"))
    )
    (net (code "30") (name "Net-(IC3-VCC)") (class "Default")
      (node (ref "C21") (pin "2") (pinfunction "2_2") (pintype "passive"))
      (node (ref "C22") (pin "2") (pinfunction "2_2") (pintype "passive"))
      (node (ref "C23") (pin "2") (pinfunction "2_2") (pintype "passive"))
      (node (ref "C24") (pin "2") (pinfunction "2_2") (pintype "passive"))
      (node (ref "IC3") (pin "2") (pinfunction "VCC_2") (pintype "power_in"))
      (node (ref "L7") (pin "2") (pinfunction "2_2") (pintype "passive"))
    )
    (net (code "31") (name "Net-(IC5-RF_IN)") (class "Default")
      (node (ref "C55") (pin "2") (pinfunction "2_2") (pintype "passive"))
      (node (ref "IC5") (pin "1") (pinfunction "RF_IN_1") (pintype "input"))
    )
    (net (code "32") (name "Net-(IC5-RF_OUT)") (class "Default")
      (node (ref "C29") (pin "1") (pinfunction "1_1") (pintype "passive"))
      (node (ref "IC5") (pin "3") (pinfunction "RF_OUT_3") (pintype "output"))
      (node (ref "L1") (pin "3") (pinfunction "3_3") (pintype "passive"))
    )
    (net (code "33") (name "Net-(IC17-IN)") (class "Default")
      (node (ref "C55") (pin "1") (pinfunction "1_1") (pintype "passive"))
      (node (ref "IC17") (pin "1") (pinfunction "IN_1") (pintype "bidirectional"))
    )
    (net (code "34") (name "Net-(IC17-OUT)") (class "Default")
      (node (ref "C36") (pin "2") (pinfunction "2_2") (pintype "passive"))
      (node (ref "IC17") (pin "2") (pinfunction "OUT_2") (pintype "bidirectional"))
    )
    (net (code "35") (name "Net-(IC23-EN)") (class "Default")
      (node (ref "IC23") (pin "5") (pinfunction "EN_5") (pintype "input"))
      (node (ref "R138") (pin "2") (pinfunction "2_2") (pintype "passive"))
    )
    (net (code "36") (name "Net-(IC23-RF1)") (class "Default")
      (node (ref "C49") (pin "1") (pinfunction "1_1") (pintype "passive"))
      (node (ref "IC23") (pin "9") (pinfunction "RF1_9") (pintype "bidirectional"))
    )
    (net (code "37") (name "Net-(IC23-RF2)") (class "Default")
      (node (ref "C47") (pin "1") (pinfunction "1_1") (pintype "passive"))
      (node (ref "IC23") (pin "12") (pinfunction "RF2_12") (pintype "bidirectional"))
    )
    (net (code "38") (name "Net-(IC23-RFC)") (class "Default")
      (node (ref "C29") (pin "2") (pinfunction "2_2") (pintype "passive"))
      (node (ref "IC23") (pin "3") (pinfunction "RFC_3") (pintype "bidirectional"))
    )
    (net (code "39") (name "Net-(IC23-VDD)") (class "Default")
      (node (ref "C38") (pin "1") (pinfunction "1_1") (pintype "passive"))
      (node (ref "C39") (pin "2") (pinfunction "2_2") (pintype "passive"))
      (node (ref "C40") (pin "2") (pinfunction "2_2") (pintype "passive"))
      (node (ref "IC23") (pin "1") (pinfunction "VDD_1") (pintype "power_in"))
      (node (ref "L6") (pin "1") (pinfunction "1_1") (pintype "passive"))
    )
    (net (code "40") (name "Net-(L1-Pad1)") (class "Default")
      (node (ref "L1") (pin "1") (pinfunction "1_1") (pintype "passive"))
      (node (ref "R137") (pin "2") (pinfunction "2_2") (pintype "passive"))
    )
    (net (code "41") (name "Net-(TR1-P)") (class "Default")
      (node (ref "R59") (pin "1") (pinfunction "1_1") (pintype "passive"))
      (node (ref "TR1") (pin "1") (pinfunction "P_1") (pintype "passive"))
    )
    (net (code "42") (name "P5V0A") (class "Default")
      (node (ref "L6") (pin "2") (pinfunction "2_2") (pintype "passive"))
      (node (ref "L7") (pin "1") (pinfunction "1_1") (pintype "passive"))
    )
    (net (code "43") (name "P7V0A") (class "Default")
      (node (ref "C12") (pin "2") (pinfunction "2_2") (pintype "passive"))
      (node (ref "C27") (pin "2") (pinfunction "2_2") (pintype "passive"))
      (node (ref "R137") (pin "1") (pinfunction "1_1") (pintype "passive"))
    )
    (net (code "44") (name "unconnected-(IC23-NC-Pad4)") (class "Default")
      (node (ref "IC23") (pin "4") (pinfunction "NC_4") (pintype "passive"))
    )
    (net (code "45") (name "unconnected-(IC23-NC-Pad6)") (class "Default")
      (node (ref "IC23") (pin "6") (pinfunction "NC_6") (pintype "passive"))
    )
    (net (code "46") (name "unconnected-(IC23-NC-Pad7)") (class "Default")
      (node (ref "IC23") (pin "7") (pinfunction "NC_7") (pintype "passive"))
    )
    (net (code "47") (name "unconnected-(IC23-NC-Pad8)") (class "Default")
      (node (ref "IC23") (pin "8") (pinfunction "NC_8") (pintype "passive"))
    )
    (net (code "48") (name "unconnected-(IC23-NC-Pad13)") (class "Default")
      (node (ref "IC23") (pin "13") (pinfunction "NC_13") (pintype "passive"))
    )
    (net (code "49") (name "unconnected-(IC23-NC-Pad14)") (class "Default")
      (node (ref "IC23") (pin "14") (pinfunction "NC_14") (pintype "passive"))
    )
    (net (code "50") (name "unconnected-(IC23-NC-Pad15)") (class "Default")
      (node (ref "IC23") (pin "15") (pinfunction "NC_15") (pintype "passive"))
    )
    (net (code "51") (name "unconnected-(IC23-NC-Pad16)") (class "Default")
      (node (ref "IC23") (pin "16") (pinfunction "NC_16") (pintype "passive"))
    )
  )
)
